# G021K-E.net
KiCad netlist of a schematic drawn in EAGLE
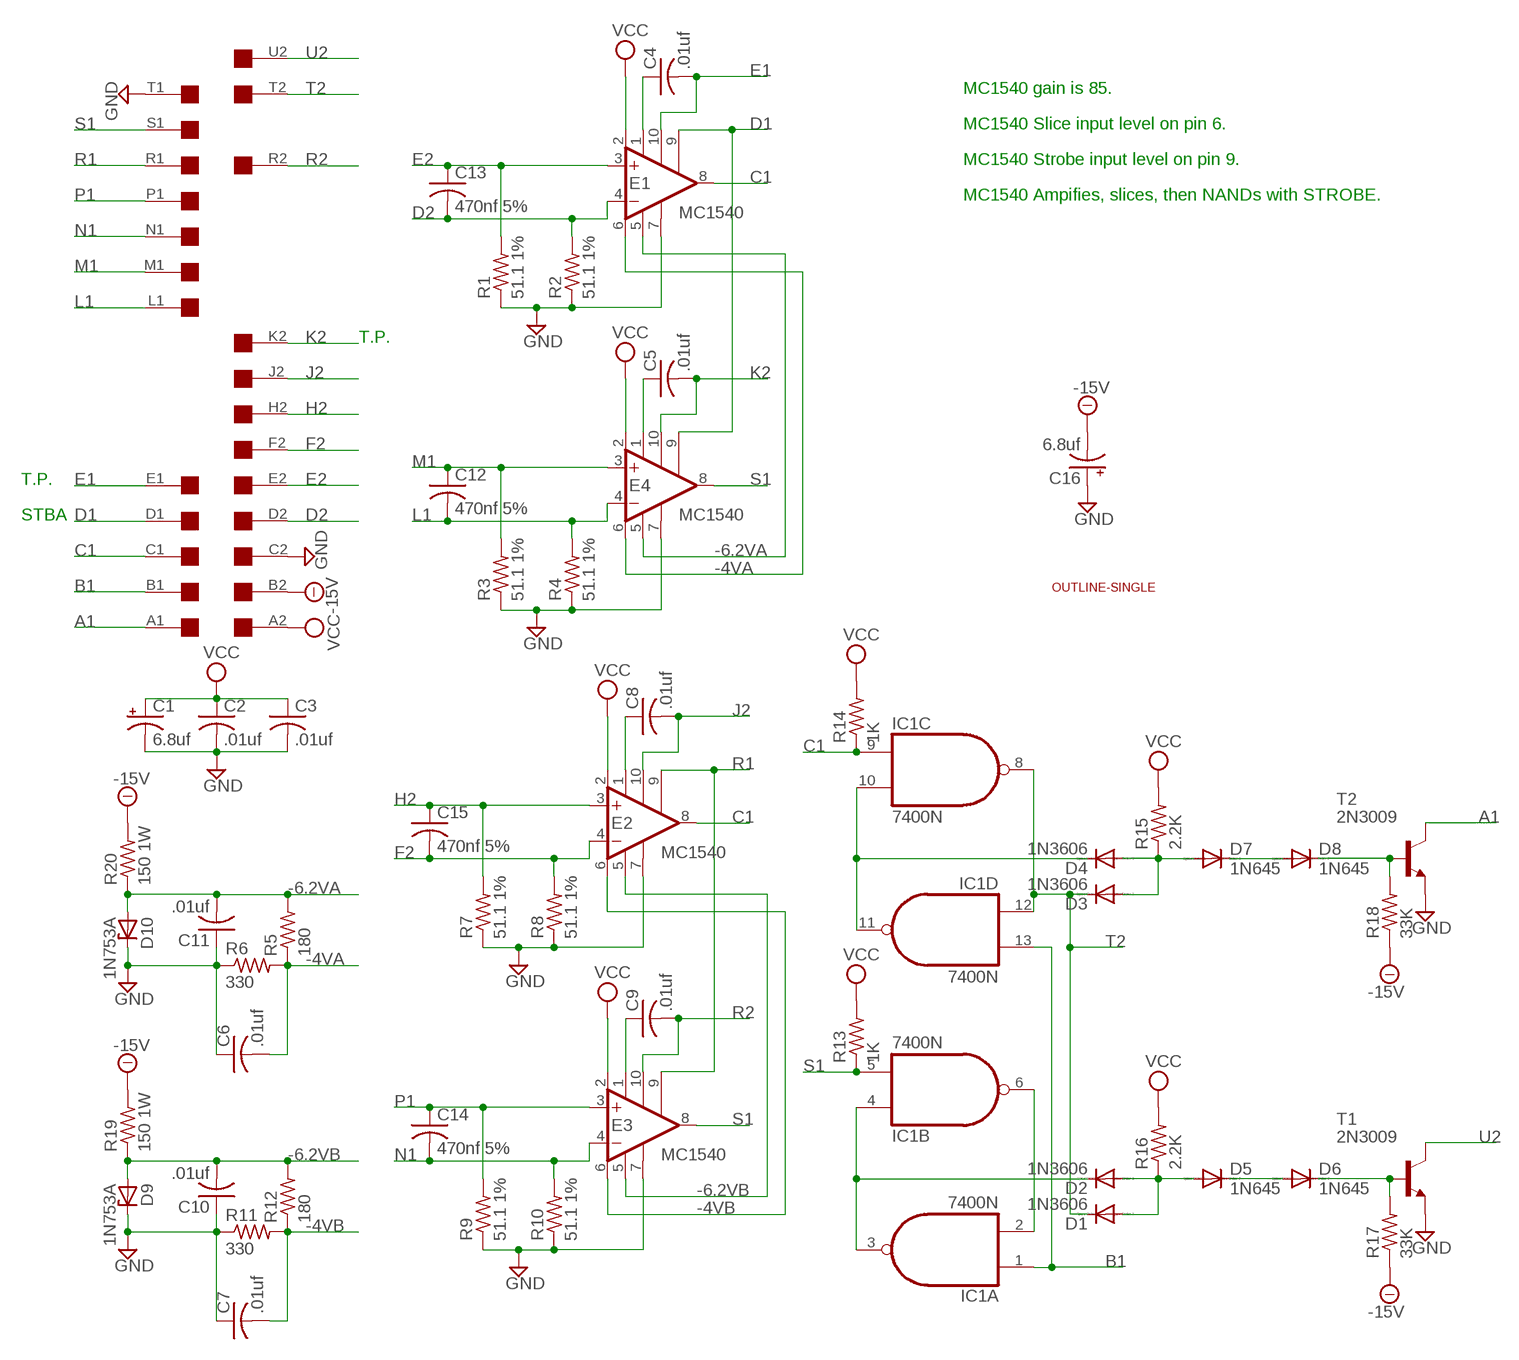
[diagram p0: schematic, sheet 1]

(export (version "E")
  (design (tool "Eeschema 10.0.6"))
  (components
    (comp (ref "C1")
      (value "6.8uf")
      (footprint "eagle-import:E15-5")
      (libsource (lib "eagle-import") (part "CPOL-USE15-5AXIAL"))
    )
    (comp (ref "C2")
      (value ".01uf")
      (footprint "eagle-import:C050-025X075")
      (libsource (lib "eagle-import") (part "C-US050-025X075"))
    )
    (comp (ref "C3")
      (value ".01uf")
      (footprint "eagle-import:C050-025X075")
      (libsource (lib "eagle-import") (part "C-US050-025X075"))
    )
    (comp (ref "C4")
      (value ".01uf")
      (footprint "eagle-import:C050-025X075")
      (libsource (lib "eagle-import") (part "C-US050-025X075"))
    )
    (comp (ref "C5")
      (value ".01uf")
      (footprint "eagle-import:C050-025X075")
      (libsource (lib "eagle-import") (part "C-US050-025X075"))
    )
    (comp (ref "C6")
      (value ".01uf")
      (footprint "eagle-import:C050-025X075")
      (libsource (lib "eagle-import") (part "C-US050-025X075"))
    )
    (comp (ref "C7")
      (value ".01uf")
      (footprint "eagle-import:C050-025X075")
      (libsource (lib "eagle-import") (part "C-US050-025X075"))
    )
    (comp (ref "C8")
      (value ".01uf")
      (footprint "eagle-import:C050-025X075")
      (libsource (lib "eagle-import") (part "C-US050-025X075"))
    )
    (comp (ref "C9")
      (value ".01uf")
      (footprint "eagle-import:C050-025X075")
      (libsource (lib "eagle-import") (part "C-US050-025X075"))
    )
    (comp (ref "C10")
      (value ".01uf")
      (footprint "eagle-import:C050-025X075")
      (libsource (lib "eagle-import") (part "C-US050-025X075"))
    )
    (comp (ref "C11")
      (value ".01uf")
      (footprint "eagle-import:C050-025X075")
      (libsource (lib "eagle-import") (part "C-US050-025X075"))
    )
    (comp (ref "C12")
      (value "470nf 5%")
      (footprint "eagle-import:C050-025X075")
      (libsource (lib "eagle-import") (part "C-US050-025X075"))
    )
    (comp (ref "C13")
      (value "470nf 5%")
      (footprint "eagle-import:C050-025X075")
      (libsource (lib "eagle-import") (part "C-US050-025X075"))
    )
    (comp (ref "C14")
      (value "470nf 5%")
      (footprint "eagle-import:C050-025X075")
      (libsource (lib "eagle-import") (part "C-US050-025X075"))
    )
    (comp (ref "C15")
      (value "470nf 5%")
      (footprint "eagle-import:C050-025X075")
      (libsource (lib "eagle-import") (part "C-US050-025X075"))
    )
    (comp (ref "C16")
      (value "6.8uf")
      (footprint "eagle-import:E15-5")
      (libsource (lib "eagle-import") (part "CPOL-USE15-5AXIAL"))
    )
    (comp (ref "D1")
      (value "1N3606")
      (footprint "eagle-import:DO35-10")
      (libsource (lib "eagle-import") (part "1N4148DO35-10"))
    )
    (comp (ref "D2")
      (value "1N3606")
      (footprint "eagle-import:DO35-10")
      (libsource (lib "eagle-import") (part "1N4148DO35-10"))
    )
    (comp (ref "D3")
      (value "1N3606")
      (footprint "eagle-import:DO35-10")
      (libsource (lib "eagle-import") (part "1N4148DO35-10"))
    )
    (comp (ref "D4")
      (value "1N3606")
      (footprint "eagle-import:DO35-10")
      (libsource (lib "eagle-import") (part "1N4148DO35-10"))
    )
    (comp (ref "D5")
      (value "1N645")
      (footprint "eagle-import:DO35-10")
      (libsource (lib "eagle-import") (part "1N4148DO35-10"))
    )
    (comp (ref "D6")
      (value "1N645")
      (footprint "eagle-import:DO35-10")
      (libsource (lib "eagle-import") (part "1N4148DO35-10"))
    )
    (comp (ref "D7")
      (value "1N645")
      (footprint "eagle-import:DO35-10")
      (libsource (lib "eagle-import") (part "1N4148DO35-10"))
    )
    (comp (ref "D8")
      (value "1N645")
      (footprint "eagle-import:DO35-10")
      (libsource (lib "eagle-import") (part "1N4148DO35-10"))
    )
    (comp (ref "D9")
      (value "1N753A")
      (footprint "eagle-import:F126Z10")
      (libsource (lib "eagle-import") (part "ZENER-DIODEF126-10"))
    )
    (comp (ref "D10")
      (value "1N753A")
      (footprint "eagle-import:F126Z10")
      (libsource (lib "eagle-import") (part "ZENER-DIODEF126-10"))
    )
    (comp (ref "E1")
      (value "MC1540")
      (footprint "eagle-import:602B")
      (libsource (lib "eagle-import") (part "MC1540G"))
    )
    (comp (ref "E2")
      (value "MC1540")
      (footprint "eagle-import:602B")
      (libsource (lib "eagle-import") (part "MC1540G"))
    )
    (comp (ref "E3")
      (value "MC1540")
      (footprint "eagle-import:602B")
      (libsource (lib "eagle-import") (part "MC1540G"))
    )
    (comp (ref "E4")
      (value "MC1540")
      (footprint "eagle-import:602B")
      (libsource (lib "eagle-import") (part "MC1540G"))
    )
    (comp (ref "IC1")
      (value "7400N")
      (footprint "eagle-import:DIL14")
      (libsource (lib "eagle-import") (part "7400N"))
    )
    (comp (ref "R1")
      (value "51.1 1%")
      (footprint "eagle-import:0207_10")
      (libsource (lib "eagle-import") (part "R-US_0207/10"))
    )
    (comp (ref "R2")
      (value "51.1 1%")
      (footprint "eagle-import:0207_10")
      (libsource (lib "eagle-import") (part "R-US_0207/10"))
    )
    (comp (ref "R3")
      (value "51.1 1%")
      (footprint "eagle-import:0207_10")
      (libsource (lib "eagle-import") (part "R-US_0207/10"))
    )
    (comp (ref "R4")
      (value "51.1 1%")
      (footprint "eagle-import:0207_10")
      (libsource (lib "eagle-import") (part "R-US_0207/10"))
    )
    (comp (ref "R5")
      (value "180")
      (footprint "eagle-import:0207_10")
      (libsource (lib "eagle-import") (part "R-US_0207/10"))
    )
    (comp (ref "R6")
      (value "330")
      (footprint "eagle-import:0207_10")
      (libsource (lib "eagle-import") (part "R-US_0207/10"))
    )
    (comp (ref "R7")
      (value "51.1 1%")
      (footprint "eagle-import:0207_10")
      (libsource (lib "eagle-import") (part "R-US_0207/10"))
    )
    (comp (ref "R8")
      (value "51.1 1%")
      (footprint "eagle-import:0207_10")
      (libsource (lib "eagle-import") (part "R-US_0207/10"))
    )
    (comp (ref "R9")
      (value "51.1 1%")
      (footprint "eagle-import:0207_10")
      (libsource (lib "eagle-import") (part "R-US_0207/10"))
    )
    (comp (ref "R10")
      (value "51.1 1%")
      (footprint "eagle-import:0207_10")
      (libsource (lib "eagle-import") (part "R-US_0207/10"))
    )
    (comp (ref "R11")
      (value "330")
      (footprint "eagle-import:0207_10")
      (libsource (lib "eagle-import") (part "R-US_0207/10"))
    )
    (comp (ref "R12")
      (value "180")
      (footprint "eagle-import:0207_10")
      (libsource (lib "eagle-import") (part "R-US_0207/10"))
    )
    (comp (ref "R13")
      (value "1K")
      (footprint "eagle-import:0207_10")
      (libsource (lib "eagle-import") (part "R-US_0207/10"))
    )
    (comp (ref "R14")
      (value "1K")
      (footprint "eagle-import:0207_10")
      (libsource (lib "eagle-import") (part "R-US_0207/10"))
    )
    (comp (ref "R15")
      (value "2.2K")
      (footprint "eagle-import:0207_10")
      (libsource (lib "eagle-import") (part "R-US_0207/10"))
    )
    (comp (ref "R16")
      (value "2.2K")
      (footprint "eagle-import:0207_10")
      (libsource (lib "eagle-import") (part "R-US_0207/10"))
    )
    (comp (ref "R17")
      (value "33K")
      (footprint "eagle-import:0207_10")
      (libsource (lib "eagle-import") (part "R-US_0207/10"))
    )
    (comp (ref "R18")
      (value "33K")
      (footprint "eagle-import:0207_10")
      (libsource (lib "eagle-import") (part "R-US_0207/10"))
    )
    (comp (ref "R19")
      (value "150 1W")
      (footprint "eagle-import:0414_15")
      (libsource (lib "eagle-import") (part "R-US_0414/15"))
    )
    (comp (ref "R20")
      (value "150 1W")
      (footprint "eagle-import:0414_15")
      (libsource (lib "eagle-import") (part "R-US_0414/15"))
    )
    (comp (ref "T1")
      (value "2N3009")
      (footprint "eagle-import:TO92")
      (libsource (lib "eagle-import") (part "2N3565"))
    )
    (comp (ref "T2")
      (value "2N3009")
      (footprint "eagle-import:TO92")
      (libsource (lib "eagle-import") (part "2N3565"))
    )
    (comp (ref "U$1")
      (value "SINGLE")
      (footprint "eagle-import:EDGE-CON2")
      (libsource (lib "eagle-import") (part "SINGLE"))
    )
    (comp (ref "U$2")
      (value "OUTLINE-SINGLE")
      (footprint "eagle-import:SINGLE")
      (libsource (lib "eagle-import") (part "OUTLINE-SINGLE"))
    )
  )
  (nets
    (net (code "1") (name "-15V") (class "Default")
      (node (ref "C16") (pin "-") (pinfunction "-_-") (pintype "passive"))
      (node (ref "R17") (pin "1") (pinfunction "1_1") (pintype "passive"))
      (node (ref "R18") (pin "1") (pinfunction "1_1") (pintype "passive"))
      (node (ref "R19") (pin "2") (pinfunction "2_2") (pintype "passive"))
      (node (ref "R20") (pin "2") (pinfunction "2_2") (pintype "passive"))
      (node (ref "U$1") (pin "B2") (pinfunction "1_B2") (pintype "bidirectional"))
    )
    (net (code "2") (name "/-4VA") (class "Default")
      (node (ref "C6") (pin "2") (pinfunction "2_2") (pintype "passive"))
      (node (ref "E1") (pin "6") (pinfunction "SLICE_6") (pintype "bidirectional"))
      (node (ref "E4") (pin "6") (pinfunction "SLICE_6") (pintype "bidirectional"))
      (node (ref "R5") (pin "1") (pinfunction "1_1") (pintype "passive"))
      (node (ref "R6") (pin "2") (pinfunction "2_2") (pintype "passive"))
    )
    (net (code "3") (name "/-4VB") (class "Default")
      (node (ref "C7") (pin "2") (pinfunction "2_2") (pintype "passive"))
      (node (ref "E2") (pin "6") (pinfunction "SLICE_6") (pintype "bidirectional"))
      (node (ref "E3") (pin "6") (pinfunction "SLICE_6") (pintype "bidirectional"))
      (node (ref "R11") (pin "2") (pinfunction "2_2") (pintype "passive"))
      (node (ref "R12") (pin "1") (pinfunction "1_1") (pintype "passive"))
    )
    (net (code "4") (name "/-6.2VA") (class "Default")
      (node (ref "C11") (pin "2") (pinfunction "2_2") (pintype "passive"))
      (node (ref "D10") (pin "A") (pinfunction "A_A") (pintype "passive"))
      (node (ref "E1") (pin "5") (pinfunction "V-_5") (pintype "power_in"))
      (node (ref "E4") (pin "5") (pinfunction "V-_5") (pintype "power_in"))
      (node (ref "R20") (pin "1") (pinfunction "1_1") (pintype "passive"))
      (node (ref "R5") (pin "2") (pinfunction "2_2") (pintype "passive"))
    )
    (net (code "5") (name "/-6.2VB") (class "Default")
      (node (ref "C10") (pin "2") (pinfunction "2_2") (pintype "passive"))
      (node (ref "D9") (pin "A") (pinfunction "A_A") (pintype "passive"))
      (node (ref "E2") (pin "5") (pinfunction "V-_5") (pintype "power_in"))
      (node (ref "E3") (pin "5") (pinfunction "V-_5") (pintype "power_in"))
      (node (ref "R12") (pin "2") (pinfunction "2_2") (pintype "passive"))
      (node (ref "R19") (pin "1") (pinfunction "1_1") (pintype "passive"))
    )
    (net (code "6") (name "/A1") (class "Default")
      (node (ref "T2") (pin "1") (pinfunction "C_1") (pintype "passive"))
      (node (ref "U$1") (pin "A1") (pinfunction "1_A1") (pintype "bidirectional"))
    )
    (net (code "7") (name "/B1") (class "Default")
      (node (ref "IC1") (pin "1") (pinfunction "I0_1") (pintype "input"))
      (node (ref "IC1") (pin "13") (pinfunction "I1_13") (pintype "input"))
      (node (ref "U$1") (pin "B1") (pinfunction "1_B1") (pintype "bidirectional"))
    )
    (net (code "8") (name "/C1") (class "Default")
      (node (ref "E1") (pin "8") (pinfunction "OUT_8") (pintype "open_collector"))
      (node (ref "E2") (pin "8") (pinfunction "OUT_8") (pintype "open_collector"))
      (node (ref "IC1") (pin "9") (pinfunction "I0_9") (pintype "input"))
      (node (ref "R14") (pin "1") (pinfunction "1_1") (pintype "passive"))
      (node (ref "U$1") (pin "C1") (pinfunction "1_C1") (pintype "bidirectional"))
    )
    (net (code "9") (name "/D1") (class "Default")
      (node (ref "E1") (pin "9") (pinfunction "ISTROBE_9") (pintype "passive"))
      (node (ref "E4") (pin "9") (pinfunction "ISTROBE_9") (pintype "passive"))
      (node (ref "U$1") (pin "D1") (pinfunction "1_D1") (pintype "bidirectional"))
    )
    (net (code "10") (name "/D2") (class "Default")
      (node (ref "C13") (pin "2") (pinfunction "2_2") (pintype "passive"))
      (node (ref "E1") (pin "4") (pinfunction "-IN_4") (pintype "input"))
      (node (ref "R2") (pin "2") (pinfunction "2_2") (pintype "passive"))
      (node (ref "U$1") (pin "D2") (pinfunction "1_D2") (pintype "bidirectional"))
    )
    (net (code "11") (name "/E1") (class "Default")
      (node (ref "C4") (pin "2") (pinfunction "2_2") (pintype "passive"))
      (node (ref "E1") (pin "10") (pinfunction "CEXTB_10") (pintype "passive"))
      (node (ref "U$1") (pin "E1") (pinfunction "1_E1") (pintype "bidirectional"))
    )
    (net (code "12") (name "/E2") (class "Default")
      (node (ref "C13") (pin "1") (pinfunction "1_1") (pintype "passive"))
      (node (ref "E1") (pin "3") (pinfunction "+IN_3") (pintype "input"))
      (node (ref "R1") (pin "2") (pinfunction "2_2") (pintype "passive"))
      (node (ref "U$1") (pin "E2") (pinfunction "1_E2") (pintype "bidirectional"))
    )
    (net (code "13") (name "/F2") (class "Default")
      (node (ref "C15") (pin "2") (pinfunction "2_2") (pintype "passive"))
      (node (ref "E2") (pin "4") (pinfunction "-IN_4") (pintype "input"))
      (node (ref "R8") (pin "2") (pinfunction "2_2") (pintype "passive"))
      (node (ref "U$1") (pin "F2") (pinfunction "1_F2") (pintype "bidirectional"))
    )
    (net (code "14") (name "/H2") (class "Default")
      (node (ref "C15") (pin "1") (pinfunction "1_1") (pintype "passive"))
      (node (ref "E2") (pin "3") (pinfunction "+IN_3") (pintype "input"))
      (node (ref "R7") (pin "2") (pinfunction "2_2") (pintype "passive"))
      (node (ref "U$1") (pin "H2") (pinfunction "1_H2") (pintype "bidirectional"))
    )
    (net (code "15") (name "/J2") (class "Default")
      (node (ref "C8") (pin "2") (pinfunction "2_2") (pintype "passive"))
      (node (ref "E2") (pin "10") (pinfunction "CEXTB_10") (pintype "passive"))
      (node (ref "U$1") (pin "J2") (pinfunction "1_J2") (pintype "bidirectional"))
    )
    (net (code "16") (name "/K2") (class "Default")
      (node (ref "C5") (pin "2") (pinfunction "2_2") (pintype "passive"))
      (node (ref "E4") (pin "10") (pinfunction "CEXTB_10") (pintype "passive"))
      (node (ref "U$1") (pin "K2") (pinfunction "1_K2") (pintype "bidirectional"))
    )
    (net (code "17") (name "/L1") (class "Default")
      (node (ref "C12") (pin "2") (pinfunction "2_2") (pintype "passive"))
      (node (ref "E4") (pin "4") (pinfunction "-IN_4") (pintype "input"))
      (node (ref "R4") (pin "2") (pinfunction "2_2") (pintype "passive"))
      (node (ref "U$1") (pin "L1") (pinfunction "1_L1") (pintype "bidirectional"))
    )
    (net (code "18") (name "/M1") (class "Default")
      (node (ref "C12") (pin "1") (pinfunction "1_1") (pintype "passive"))
      (node (ref "E4") (pin "3") (pinfunction "+IN_3") (pintype "input"))
      (node (ref "R3") (pin "2") (pinfunction "2_2") (pintype "passive"))
      (node (ref "U$1") (pin "M1") (pinfunction "1_M1") (pintype "bidirectional"))
    )
    (net (code "19") (name "/N1") (class "Default")
      (node (ref "C14") (pin "2") (pinfunction "2_2") (pintype "passive"))
      (node (ref "E3") (pin "4") (pinfunction "-IN_4") (pintype "input"))
      (node (ref "R10") (pin "2") (pinfunction "2_2") (pintype "passive"))
      (node (ref "U$1") (pin "N1") (pinfunction "1_N1") (pintype "bidirectional"))
    )
    (net (code "20") (name "/P1") (class "Default")
      (node (ref "C14") (pin "1") (pinfunction "1_1") (pintype "passive"))
      (node (ref "E3") (pin "3") (pinfunction "+IN_3") (pintype "input"))
      (node (ref "R9") (pin "2") (pinfunction "2_2") (pintype "passive"))
      (node (ref "U$1") (pin "P1") (pinfunction "1_P1") (pintype "bidirectional"))
    )
    (net (code "21") (name "/R1") (class "Default")
      (node (ref "E2") (pin "9") (pinfunction "ISTROBE_9") (pintype "passive"))
      (node (ref "E3") (pin "9") (pinfunction "ISTROBE_9") (pintype "passive"))
      (node (ref "U$1") (pin "R1") (pinfunction "1_R1") (pintype "bidirectional"))
    )
    (net (code "22") (name "/R2") (class "Default")
      (node (ref "C9") (pin "2") (pinfunction "2_2") (pintype "passive"))
      (node (ref "E3") (pin "10") (pinfunction "CEXTB_10") (pintype "passive"))
      (node (ref "U$1") (pin "R2") (pinfunction "1_R2") (pintype "bidirectional"))
    )
    (net (code "23") (name "/S1") (class "Default")
      (node (ref "E3") (pin "8") (pinfunction "OUT_8") (pintype "open_collector"))
      (node (ref "E4") (pin "8") (pinfunction "OUT_8") (pintype "open_collector"))
      (node (ref "IC1") (pin "5") (pinfunction "I1_5") (pintype "input"))
      (node (ref "R13") (pin "1") (pinfunction "1_1") (pintype "passive"))
      (node (ref "U$1") (pin "S1") (pinfunction "1_S1") (pintype "bidirectional"))
    )
    (net (code "24") (name "/T2") (class "Default")
      (node (ref "D1") (pin "C") (pinfunction "C_C") (pintype "passive"))
      (node (ref "D3") (pin "C") (pinfunction "C_C") (pintype "passive"))
      (node (ref "IC1") (pin "12") (pinfunction "I0_12") (pintype "input"))
      (node (ref "IC1") (pin "8") (pinfunction "O_8") (pintype "output"))
      (node (ref "U$1") (pin "T2") (pinfunction "1_T2") (pintype "bidirectional"))
    )
    (net (code "25") (name "/U2") (class "Default")
      (node (ref "T1") (pin "1") (pinfunction "C_1") (pintype "passive"))
      (node (ref "U$1") (pin "U2") (pinfunction "1_U2") (pintype "bidirectional"))
    )
    (net (code "26") (name "GND") (class "Default")
      (node (ref "C1") (pin "-") (pinfunction "-_-") (pintype "passive"))
      (node (ref "C10") (pin "1") (pinfunction "1_1") (pintype "passive"))
      (node (ref "C11") (pin "1") (pinfunction "1_1") (pintype "passive"))
      (node (ref "C16") (pin "+") (pinfunction "+_+") (pintype "passive"))
      (node (ref "C2") (pin "2") (pinfunction "2_2") (pintype "passive"))
      (node (ref "C3") (pin "2") (pinfunction "2_2") (pintype "passive"))
      (node (ref "C6") (pin "1") (pinfunction "1_1") (pintype "passive"))
      (node (ref "C7") (pin "1") (pinfunction "1_1") (pintype "passive"))
      (node (ref "D10") (pin "C") (pinfunction "C_C") (pintype "passive"))
      (node (ref "D9") (pin "C") (pinfunction "C_C") (pintype "passive"))
      (node (ref "E1") (pin "7") (pinfunction "GND_7") (pintype "power_in"))
      (node (ref "E2") (pin "7") (pinfunction "GND_7") (pintype "power_in"))
      (node (ref "E3") (pin "7") (pinfunction "GND_7") (pintype "power_in"))
      (node (ref "E4") (pin "7") (pinfunction "GND_7") (pintype "power_in"))
      (node (ref "R1") (pin "1") (pinfunction "1_1") (pintype "passive"))
      (node (ref "R10") (pin "1") (pinfunction "1_1") (pintype "passive"))
      (node (ref "R11") (pin "1") (pinfunction "1_1") (pintype "passive"))
      (node (ref "R2") (pin "1") (pinfunction "1_1") (pintype "passive"))
      (node (ref "R3") (pin "1") (pinfunction "1_1") (pintype "passive"))
      (node (ref "R4") (pin "1") (pinfunction "1_1") (pintype "passive"))
      (node (ref "R6") (pin "1") (pinfunction "1_1") (pintype "passive"))
      (node (ref "R7") (pin "1") (pinfunction "1_1") (pintype "passive"))
      (node (ref "R8") (pin "1") (pinfunction "1_1") (pintype "passive"))
      (node (ref "R9") (pin "1") (pinfunction "1_1") (pintype "passive"))
      (node (ref "T1") (pin "3") (pinfunction "E_3") (pintype "passive"))
      (node (ref "T2") (pin "3") (pinfunction "E_3") (pintype "passive"))
      (node (ref "U$1") (pin "C2") (pinfunction "1_C2") (pintype "bidirectional"))
      (node (ref "U$1") (pin "T1") (pinfunction "1_T1") (pintype "bidirectional"))
    )
    (net (code "27") (name "Net-(D1-PadA)") (class "Default")
      (node (ref "D1") (pin "A") (pinfunction "A_A") (pintype "passive"))
      (node (ref "D2") (pin "A") (pinfunction "A_A") (pintype "passive"))
      (node (ref "D5") (pin "A") (pinfunction "A_A") (pintype "passive"))
      (node (ref "R16") (pin "1") (pinfunction "1_1") (pintype "passive"))
    )
    (net (code "28") (name "Net-(D3-PadA)") (class "Default")
      (node (ref "D3") (pin "A") (pinfunction "A_A") (pintype "passive"))
      (node (ref "D4") (pin "A") (pinfunction "A_A") (pintype "passive"))
      (node (ref "D7") (pin "A") (pinfunction "A_A") (pintype "passive"))
      (node (ref "R15") (pin "1") (pinfunction "1_1") (pintype "passive"))
    )
    (net (code "29") (name "Net-(D5-PadC)") (class "Default")
      (node (ref "D5") (pin "C") (pinfunction "C_C") (pintype "passive"))
      (node (ref "D6") (pin "A") (pinfunction "A_A") (pintype "passive"))
    )
    (net (code "30") (name "Net-(D7-PadC)") (class "Default")
      (node (ref "D7") (pin "C") (pinfunction "C_C") (pintype "passive"))
      (node (ref "D8") (pin "A") (pinfunction "A_A") (pintype "passive"))
    )
    (net (code "31") (name "Net-(E1-CEXTA)") (class "Default")
      (node (ref "C4") (pin "1") (pinfunction "1_1") (pintype "passive"))
      (node (ref "E1") (pin "1") (pinfunction "CEXTA_1") (pintype "passive"))
    )
    (net (code "32") (name "Net-(E2-CEXTA)") (class "Default")
      (node (ref "C8") (pin "1") (pinfunction "1_1") (pintype "passive"))
      (node (ref "E2") (pin "1") (pinfunction "CEXTA_1") (pintype "passive"))
    )
    (net (code "33") (name "Net-(E3-CEXTA)") (class "Default")
      (node (ref "C9") (pin "1") (pinfunction "1_1") (pintype "passive"))
      (node (ref "E3") (pin "1") (pinfunction "CEXTA_1") (pintype "passive"))
    )
    (net (code "34") (name "Net-(E4-CEXTA)") (class "Default")
      (node (ref "C5") (pin "1") (pinfunction "1_1") (pintype "passive"))
      (node (ref "E4") (pin "1") (pinfunction "CEXTA_1") (pintype "passive"))
    )
    (net (code "35") (name "Net-(IC1A-I1)") (class "Default")
      (node (ref "IC1") (pin "2") (pinfunction "I1_2") (pintype "input"))
      (node (ref "IC1") (pin "6") (pinfunction "O_6") (pintype "output"))
    )
    (net (code "36") (name "Net-(IC1A-O)") (class "Default")
      (node (ref "D2") (pin "C") (pinfunction "C_C") (pintype "passive"))
      (node (ref "IC1") (pin "3") (pinfunction "O_3") (pintype "output"))
      (node (ref "IC1") (pin "4") (pinfunction "I0_4") (pintype "input"))
    )
    (net (code "37") (name "Net-(IC1C-I1)") (class "Default")
      (node (ref "D4") (pin "C") (pinfunction "C_C") (pintype "passive"))
      (node (ref "IC1") (pin "10") (pinfunction "I1_10") (pintype "input"))
      (node (ref "IC1") (pin "11") (pinfunction "O_11") (pintype "output"))
    )
    (net (code "38") (name "Net-(T1-B)") (class "Default")
      (node (ref "D6") (pin "C") (pinfunction "C_C") (pintype "passive"))
      (node (ref "R17") (pin "2") (pinfunction "2_2") (pintype "passive"))
      (node (ref "T1") (pin "2") (pinfunction "B_2") (pintype "passive"))
    )
    (net (code "39") (name "Net-(T2-B)") (class "Default")
      (node (ref "D8") (pin "C") (pinfunction "C_C") (pintype "passive"))
      (node (ref "R18") (pin "2") (pinfunction "2_2") (pintype "passive"))
      (node (ref "T2") (pin "2") (pinfunction "B_2") (pintype "passive"))
    )
    (net (code "40") (name "VCC") (class "Default")
      (node (ref "C1") (pin "+") (pinfunction "+_+") (pintype "passive"))
      (node (ref "C2") (pin "1") (pinfunction "1_1") (pintype "passive"))
      (node (ref "C3") (pin "1") (pinfunction "1_1") (pintype "passive"))
      (node (ref "E1") (pin "2") (pinfunction "V+_2") (pintype "power_in"))
      (node (ref "E2") (pin "2") (pinfunction "V+_2") (pintype "power_in"))
      (node (ref "E3") (pin "2") (pinfunction "V+_2") (pintype "power_in"))
      (node (ref "E4") (pin "2") (pinfunction "V+_2") (pintype "power_in"))
      (node (ref "R13") (pin "2") (pinfunction "2_2") (pintype "passive"))
      (node (ref "R14") (pin "2") (pinfunction "2_2") (pintype "passive"))
      (node (ref "R15") (pin "2") (pinfunction "2_2") (pintype "passive"))
      (node (ref "R16") (pin "2") (pinfunction "2_2") (pintype "passive"))
      (node (ref "U$1") (pin "A2") (pinfunction "1_A2") (pintype "bidirectional"))
    )
  )
)
